# PortableWiFiRepeaterUSBPowerOnly.net
KiCad netlist of a schematic drawn in EAGLE
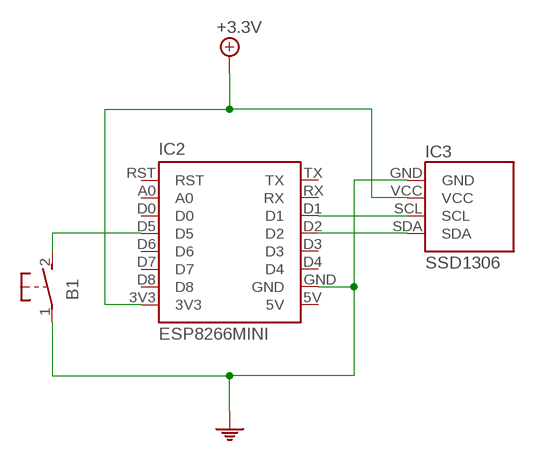
[diagram p0: schematic, sheet 1]

(export (version "E")
  (design (tool "Eeschema 10.0.6"))
  (components
    (comp (ref "B1")
      (value "BUTTONSIL2")
      (footprint "eagle-import:SIL2")
      (libsource (lib "eagle-import") (part "BUTTONSIL2"))
    )
    (comp (ref "IC2")
      (value "ESP8266MINI")
      (footprint "eagle-import:ESP8266MINI")
      (libsource (lib "eagle-import") (part "ESP8266MINI"))
    )
    (comp (ref "IC3")
      (value "SSD1306")
      (footprint "eagle-import:SSD1306")
      (libsource (lib "eagle-import") (part "SSD1306"))
    )
  )
  (nets
    (net (code "1") (name "+3.3V") (class "Default")
      (node (ref "IC2") (pin "3V3") (pinfunction "3V3_3V3") (pintype "power_in"))
      (node (ref "IC3") (pin "VCC") (pinfunction "VCC_VCC") (pintype "power_in"))
    )
    (net (code "2") (name "/5V") (class "Default")
      (node (ref "IC2") (pin "5V") (pinfunction "5V_5V") (pintype "power_in"))
    )
    (net (code "3") (name "GND") (class "Default")
      (node (ref "B1") (pin "1") (pinfunction "P_1") (pintype "passive"))
      (node (ref "IC2") (pin "GND") (pinfunction "GND_GND") (pintype "power_in"))
      (node (ref "IC3") (pin "GND") (pinfunction "GND_GND") (pintype "power_in"))
    )
    (net (code "4") (name "Net-(B1-S)") (class "Default")
      (node (ref "B1") (pin "2") (pinfunction "S_2") (pintype "passive"))
      (node (ref "IC2") (pin "D5") (pinfunction "D5_D5") (pintype "bidirectional"))
    )
    (net (code "5") (name "Net-(IC2-PadD1)") (class "Default")
      (node (ref "IC2") (pin "D1") (pinfunction "D1_D1") (pintype "bidirectional"))
      (node (ref "IC3") (pin "SCL") (pinfunction "SCL_SCL") (pintype "bidirectional"))
    )
    (net (code "6") (name "Net-(IC2-PadD2)") (class "Default")
      (node (ref "IC2") (pin "D2") (pinfunction "D2_D2") (pintype "bidirectional"))
      (node (ref "IC3") (pin "SDA") (pinfunction "SDA_SDA") (pintype "bidirectional"))
    )
    (net (code "7") (name "unconnected-(IC2-PadA0)") (class "Default")
      (node (ref "IC2") (pin "A0") (pinfunction "A0_A0") (pintype "bidirectional"))
    )
    (net (code "8") (name "unconnected-(IC2-PadD0)") (class "Default")
      (node (ref "IC2") (pin "D0") (pinfunction "D0_D0") (pintype "bidirectional"))
    )
    (net (code "9") (name "unconnected-(IC2-PadD3)") (class "Default")
      (node (ref "IC2") (pin "D3") (pinfunction "D3_D3") (pintype "bidirectional"))
    )
    (net (code "10") (name "unconnected-(IC2-PadD4)") (class "Default")
      (node (ref "IC2") (pin "D4") (pinfunction "D4_D4") (pintype "bidirectional"))
    )
    (net (code "11") (name "unconnected-(IC2-PadD6)") (class "Default")
      (node (ref "IC2") (pin "D6") (pinfunction "D6_D6") (pintype "bidirectional"))
    )
    (net (code "12") (name "unconnected-(IC2-PadD7)") (class "Default")
      (node (ref "IC2") (pin "D7") (pinfunction "D7_D7") (pintype "bidirectional"))
    )
    (net (code "13") (name "unconnected-(IC2-PadD8)") (class "Default")
      (node (ref "IC2") (pin "D8") (pinfunction "D8_D8") (pintype "bidirectional"))
    )
    (net (code "14") (name "unconnected-(IC2-PadRST)") (class "Default")
      (node (ref "IC2") (pin "RST") (pinfunction "RST_RST") (pintype "bidirectional"))
    )
    (net (code "15") (name "unconnected-(IC2-PadRX)") (class "Default")
      (node (ref "IC2") (pin "RX") (pinfunction "RX_RX") (pintype "input"))
    )
    (net (code "16") (name "unconnected-(IC2-PadTX)") (class "Default")
      (node (ref "IC2") (pin "TX") (pinfunction "TX_TX") (pintype "output"))
    )
  )
)
